# Headphone-Amplifier-ClassAB-long.net
KiCad netlist of a schematic drawn in EAGLE
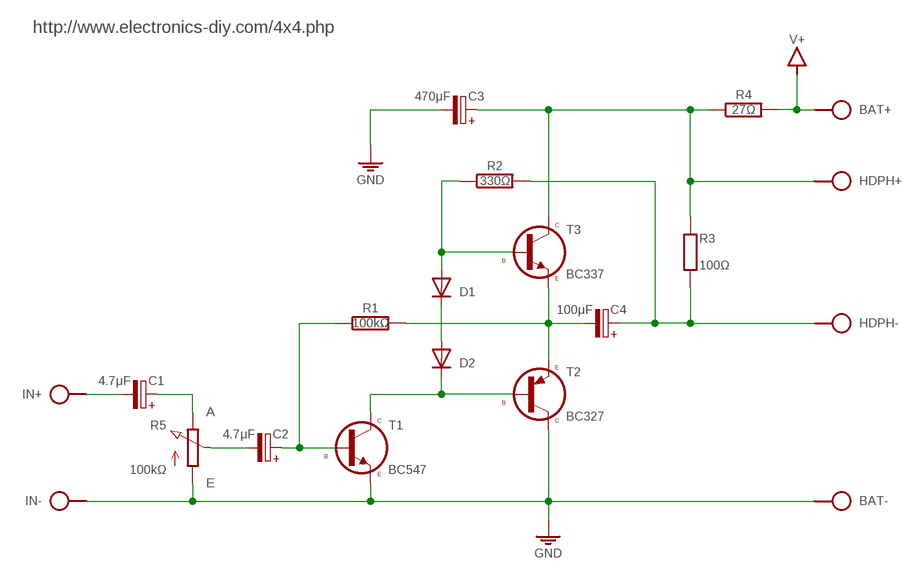
[diagram p0: schematic, sheet 1]

(export (version "E")
  (design (tool "Eeschema 10.0.6"))
  (components
    (comp (ref "BAT")
      (value "SPAD+-+-")
      (footprint "eagle-import:SPAD+-")
      (libsource (lib "eagle-import") (part "SPAD+-+-"))
    )
    (comp (ref "C1")
      (value "4.7μF")
      (footprint "eagle-import:E2,5-4")
      (libsource (lib "eagle-import") (part "CPOL-HE2,5-4"))
    )
    (comp (ref "C2")
      (value "4.7μF")
      (footprint "eagle-import:E2,5-4")
      (libsource (lib "eagle-import") (part "CPOL-HE2,5-4"))
    )
    (comp (ref "C3")
      (value "470μF")
      (footprint "eagle-import:E5-5_V")
      (libsource (lib "eagle-import") (part "CPOL-HE5-5/V"))
    )
    (comp (ref "C4")
      (value "100μF")
      (footprint "eagle-import:E5-4")
      (libsource (lib "eagle-import") (part "CPOL-HE5-4"))
    )
    (comp (ref "D1")
      (value "1N414834-5V")
      (footprint "eagle-import:DO34-5V")
      (libsource (lib "eagle-import") (part "1N414834-5V"))
    )
    (comp (ref "D2")
      (value "1N414834-5V")
      (footprint "eagle-import:DO34-5V")
      (libsource (lib "eagle-import") (part "1N414834-5V"))
    )
    (comp (ref "HDPH")
      (value "SPAD+--+")
      (footprint "eagle-import:SPAD-+")
      (libsource (lib "eagle-import") (part "SPAD+--+"))
    )
    (comp (ref "IN")
      (value "SPAD+--+")
      (footprint "eagle-import:SPAD-+")
      (libsource (lib "eagle-import") (part "SPAD+--+"))
    )
    (comp (ref "R1")
      (value "100kΩ")
      (footprint "eagle-import:0202_7")
      (libsource (lib "eagle-import") (part "R-H0202/7"))
    )
    (comp (ref "R2")
      (value "330Ω")
      (footprint "eagle-import:0202_7")
      (libsource (lib "eagle-import") (part "R-H0202/7"))
    )
    (comp (ref "R3")
      (value "100Ω")
      (footprint "eagle-import:0202_7")
      (libsource (lib "eagle-import") (part "R0202/7"))
    )
    (comp (ref "R4")
      (value "27Ω")
      (footprint "eagle-import:0204_2V")
      (libsource (lib "eagle-import") (part "R-H0204/2V"))
    )
    (comp (ref "R5")
      (value "100kΩ")
      (footprint "eagle-import:CONN-3P")
      (libsource (lib "eagle-import") (part "POT-3P"))
    )
    (comp (ref "T1")
      (value "BC547")
      (footprint "eagle-import:TO92")
      (libsource (lib "eagle-import") (part "BC547"))
    )
    (comp (ref "T2")
      (value "BC327")
      (footprint "eagle-import:TO92")
      (libsource (lib "eagle-import") (part "BC327"))
    )
    (comp (ref "T3")
      (value "BC337")
      (footprint "eagle-import:TO92-CBE")
      (libsource (lib "eagle-import") (part "BC337CBE"))
    )
  )
  (nets
    (net (code "1") (name "GND") (class "Default")
      (node (ref "BAT") (pin "1") (pinfunction "P$1_1") (pintype "passive"))
      (node (ref "C3") (pin "-") (pinfunction "-_-") (pintype "passive"))
      (node (ref "IN") (pin "1") (pinfunction "P$1_1") (pintype "passive"))
      (node (ref "R5") (pin "1") (pinfunction "A_1") (pintype "passive"))
      (node (ref "T1") (pin "3") (pinfunction "E_3") (pintype "passive"))
      (node (ref "T2") (pin "1") (pinfunction "C_1") (pintype "passive"))
    )
    (net (code "2") (name "Net-(D1-PadC)") (class "Default")
      (node (ref "D1") (pin "C") (pinfunction "C_C") (pintype "passive"))
      (node (ref "D2") (pin "A") (pinfunction "A_A") (pintype "passive"))
    )
    (net (code "3") (name "Net-(HDPHA-P$1)") (class "Default")
      (node (ref "C3") (pin "+") (pinfunction "+_+") (pintype "passive"))
      (node (ref "HDPH") (pin "2") (pinfunction "P$1_2") (pintype "passive"))
      (node (ref "R3") (pin "1") (pinfunction "1_1") (pintype "passive"))
      (node (ref "R4") (pin "1") (pinfunction "1_1") (pintype "passive"))
      (node (ref "T3") (pin "1") (pinfunction "C_1") (pintype "passive"))
    )
    (net (code "4") (name "Net-(HDPHB-P$1)") (class "Default")
      (node (ref "C4") (pin "+") (pinfunction "+_+") (pintype "passive"))
      (node (ref "HDPH") (pin "1") (pinfunction "P$1_1") (pintype "passive"))
      (node (ref "R2") (pin "2") (pinfunction "2_2") (pintype "passive"))
      (node (ref "R3") (pin "2") (pinfunction "2_2") (pintype "passive"))
    )
    (net (code "5") (name "Net-(INA-P$1)") (class "Default")
      (node (ref "C1") (pin "-") (pinfunction "-_-") (pintype "passive"))
      (node (ref "IN") (pin "2") (pinfunction "P$1_2") (pintype "passive"))
    )
    (net (code "6") (name "Net-(R5-E)") (class "Default")
      (node (ref "C1") (pin "+") (pinfunction "+_+") (pintype "passive"))
      (node (ref "R5") (pin "3") (pinfunction "E_3") (pintype "passive"))
    )
    (net (code "7") (name "Net-(R5-S)") (class "Default")
      (node (ref "C2") (pin "-") (pinfunction "-_-") (pintype "passive"))
      (node (ref "R5") (pin "2") (pinfunction "S_2") (pintype "passive"))
    )
    (net (code "8") (name "Net-(T1-B)") (class "Default")
      (node (ref "C2") (pin "+") (pinfunction "+_+") (pintype "passive"))
      (node (ref "R1") (pin "1") (pinfunction "1_1") (pintype "passive"))
      (node (ref "T1") (pin "2") (pinfunction "B_2") (pintype "passive"))
    )
    (net (code "9") (name "Net-(T1-C)") (class "Default")
      (node (ref "D2") (pin "C") (pinfunction "C_C") (pintype "passive"))
      (node (ref "T1") (pin "1") (pinfunction "C_1") (pintype "passive"))
      (node (ref "T2") (pin "2") (pinfunction "B_2") (pintype "passive"))
    )
    (net (code "10") (name "Net-(T2-E)") (class "Default")
      (node (ref "C4") (pin "-") (pinfunction "-_-") (pintype "passive"))
      (node (ref "R1") (pin "2") (pinfunction "2_2") (pintype "passive"))
      (node (ref "T2") (pin "3") (pinfunction "E_3") (pintype "passive"))
      (node (ref "T3") (pin "3") (pinfunction "E_3") (pintype "passive"))
    )
    (net (code "11") (name "Net-(T3-B)") (class "Default")
      (node (ref "D1") (pin "A") (pinfunction "A_A") (pintype "passive"))
      (node (ref "R2") (pin "1") (pinfunction "1_1") (pintype "passive"))
      (node (ref "T3") (pin "2") (pinfunction "B_2") (pintype "passive"))
    )
    (net (code "12") (name "V+") (class "Default")
      (node (ref "BAT") (pin "2") (pinfunction "P$1_2") (pintype "passive"))
      (node (ref "R4") (pin "2") (pinfunction "2_2") (pintype "passive"))
    )
  )
)
